# stm32.net
KiCad netlist of a schematic drawn in Altium Designer
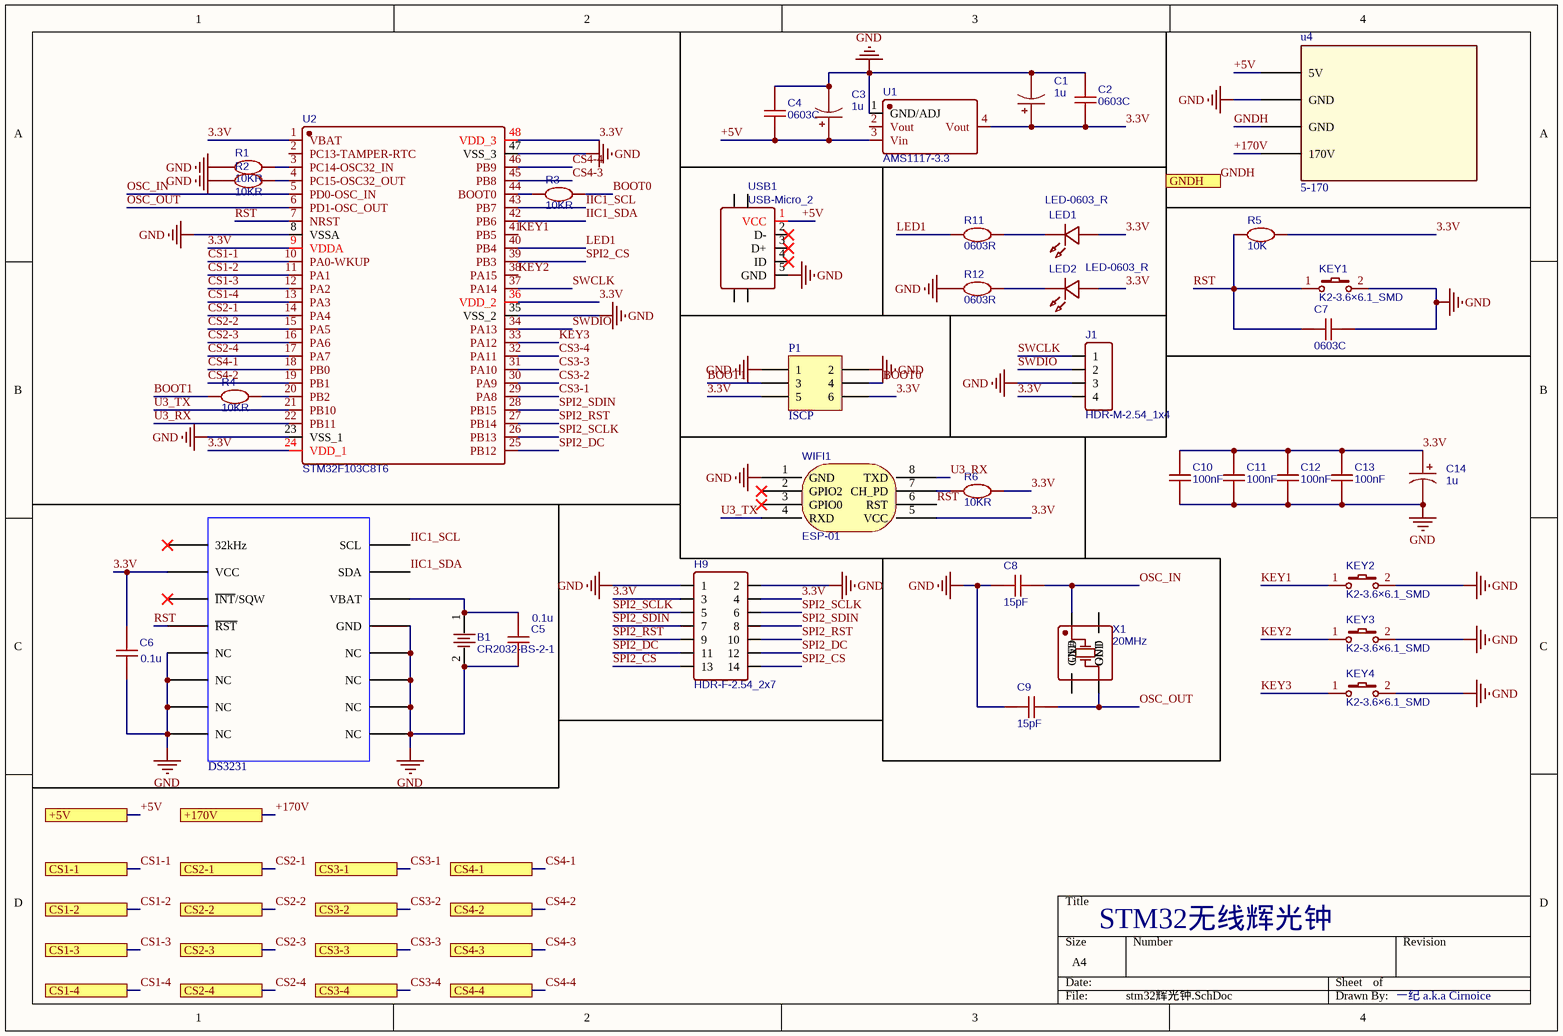
[diagram p0: stm32辉光钟.SchDoc]

(export (version "E")
  (design (tool "Eeschema 10.0.6"))
  (components
    (comp (ref "B1")
      (value "CR2032-BS-2-1")
      (footprint "BAT-TH_BS-2-1")
      (fields (field (name "BOM_MANUFACTURER PART") "BS-2-1") (field (name "BOM_SUPPLIER PART") "C70376"))
      (libsource (lib "Nixie_ESP32") (part "CR2032-BS-2-1"))
    )
    (comp (ref "C1")
      (value "1u")
      (footprint "CASE-A_3216")
      (fields (field (name "CONTRIBUTOR") "LCEDA_Lib"))
      (libsource (lib "Nixie_ESP32") (part "1u"))
    )
    (comp (ref "C2")
      (value "0603C")
      (footprint "C0603")
      (fields (field (name "CONTRIBUTOR") "LCEDA_Lib"))
      (libsource (lib "Nixie_ESP32") (part "0603C"))
    )
    (comp (ref "C3")
      (value "1u")
      (footprint "CASE-A_3216")
      (fields (field (name "CONTRIBUTOR") "LCEDA_Lib"))
      (libsource (lib "Nixie_ESP32") (part "1u"))
    )
    (comp (ref "C4")
      (value "0603C")
      (footprint "C0603")
      (fields (field (name "CONTRIBUTOR") "LCEDA_Lib"))
      (libsource (lib "Nixie_ESP32") (part "0603C"))
    )
    (comp (ref "C5")
      (value "0.1u")
      (footprint "C0603")
      (fields (field (name "CONTRIBUTOR") "LCEDA_Lib"))
      (libsource (lib "Nixie_ESP32") (part "0603C"))
    )
    (comp (ref "C6")
      (value "0.1u")
      (footprint "C0603")
      (fields (field (name "CONTRIBUTOR") "LCEDA_Lib"))
      (libsource (lib "Nixie_ESP32") (part "0603C"))
    )
    (comp (ref "C7")
      (value "0603C")
      (footprint "C0603")
      (fields (field (name "CONTRIBUTOR") "LCEDA_Lib"))
      (libsource (lib "Nixie_ESP32") (part "0603C"))
    )
    (comp (ref "C8")
      (value "15pF")
      (footprint "C0603")
      (fields (field (name "CONTRIBUTOR") "LCEDA_Lib"))
      (libsource (lib "Nixie_ESP32") (part "0603C"))
    )
    (comp (ref "C9")
      (value "15pF")
      (footprint "C0603")
      (fields (field (name "CONTRIBUTOR") "LCEDA_Lib"))
      (libsource (lib "Nixie_ESP32") (part "0603C"))
    )
    (comp (ref "C10")
      (value "100nF")
      (footprint "C0603")
      (fields (field (name "CONTRIBUTOR") "LCEDA_Lib"))
      (libsource (lib "Nixie_ESP32") (part "0603C"))
    )
    (comp (ref "C11")
      (value "100nF")
      (footprint "C0603")
      (fields (field (name "CONTRIBUTOR") "LCEDA_Lib"))
      (libsource (lib "Nixie_ESP32") (part "0603C"))
    )
    (comp (ref "C12")
      (value "100nF")
      (footprint "C0603")
      (fields (field (name "CONTRIBUTOR") "LCEDA_Lib"))
      (libsource (lib "Nixie_ESP32") (part "0603C"))
    )
    (comp (ref "C13")
      (value "100nF")
      (footprint "C0603")
      (fields (field (name "CONTRIBUTOR") "LCEDA_Lib"))
      (libsource (lib "Nixie_ESP32") (part "0603C"))
    )
    (comp (ref "C14")
      (value "1u")
      (footprint "CASE-A_3216")
      (fields (field (name "CONTRIBUTOR") "LCEDA_Lib"))
      (libsource (lib "Nixie_ESP32") (part "1u"))
    )
    (comp (ref "ds1") (value "DS3231") (footprint "DS3231") (libsource (lib "Nixie_ESP32") (part "DS3231")))
    (comp (ref "H9")
      (value "HDR-F-2.54_2x7")
      (footprint "HDR-F-2.54_2X7")
      (fields (field (name "BOM_SUPPLIER PART") "C38844") (field (name "CONTRIBUTOR") "LCEDA_Lib"))
      (libsource (lib "Nixie_ESP32") (part "HDR-F-2.54_2x7"))
    )
    (comp (ref "J1")
      (value "HDR-M-2.54_1x4")
      (footprint "HDR-M-2.54_1X4")
      (fields (field (name "BOM_SUPPLIER PART") "C124378") (field (name "CONTRIBUTOR") "LCEDA_Lib"))
      (libsource (lib "Nixie_ESP32") (part "HDR-M-2.54_1x4"))
    )
    (comp (ref "KEY1")
      (value "K2-3.6×6.1_SMD")
      (footprint "KEY-SMD_2P-L6.2-W3.6-LS8.0")
      (fields
        (field (name "BOM_SUPPLIER PART") "C118141")
        (field (name "BOM_MANUFACTURER PART") "K2-1107ST-A4SW-06")
        (field (name "CONTRIBUTOR") "LCEDA_Lib")
      )
      (libsource (lib "Nixie_ESP32") (part "K2-3.6×6.1_SMD"))
    )
    (comp (ref "KEY2")
      (value "K2-3.6×6.1_SMD")
      (footprint "KEY-SMD_2P-L6.2-W3.6-LS8.0")
      (fields
        (field (name "BOM_SUPPLIER PART") "C118141")
        (field (name "BOM_MANUFACTURER PART") "K2-1107ST-A4SW-06")
        (field (name "CONTRIBUTOR") "LCEDA_Lib")
      )
      (libsource (lib "Nixie_ESP32") (part "K2-3.6×6.1_SMD"))
    )
    (comp (ref "KEY3")
      (value "K2-3.6×6.1_SMD")
      (footprint "KEY-SMD_2P-L6.2-W3.6-LS8.0")
      (fields
        (field (name "BOM_SUPPLIER PART") "C118141")
        (field (name "BOM_MANUFACTURER PART") "K2-1107ST-A4SW-06")
        (field (name "CONTRIBUTOR") "LCEDA_Lib")
      )
      (libsource (lib "Nixie_ESP32") (part "K2-3.6×6.1_SMD"))
    )
    (comp (ref "KEY4")
      (value "K2-3.6×6.1_SMD")
      (footprint "KEY-SMD_2P-L6.2-W3.6-LS8.0")
      (fields
        (field (name "BOM_SUPPLIER PART") "C118141")
        (field (name "BOM_MANUFACTURER PART") "K2-1107ST-A4SW-06")
        (field (name "CONTRIBUTOR") "LCEDA_Lib")
      )
      (libsource (lib "Nixie_ESP32") (part "K2-3.6×6.1_SMD"))
    )
    (comp (ref "LED1")
      (value "LED-0603_R")
      (footprint "LED0603_RED")
      (fields
        (field (name "BOM_MANUFACTURER PART") "19-217/R6C-AL1M2VY/3T")
        (field (name "BOM_SUPPLIER PART") "C72044")
        (field (name "CONTRIBUTOR") "LCEDA_01")
      )
      (libsource (lib "Nixie_ESP32") (part "LED-0603_R"))
    )
    (comp (ref "LED2")
      (value "LED-0603_R")
      (footprint "LED0603_RED")
      (fields
        (field (name "BOM_MANUFACTURER PART") "19-217/R6C-AL1M2VY/3T")
        (field (name "BOM_SUPPLIER PART") "C72044")
        (field (name "CONTRIBUTOR") "LCEDA_01")
      )
      (libsource (lib "Nixie_ESP32") (part "LED-0603_R"))
    )
    (comp (ref "P1")
      (value "ISCP")
      (footprint "HDR2X3")
      (description "Header, 3-Pin, Dual row")
      (fields (field (name "PUBLISHER") "Altium Limited"))
      (libsource (lib "Nixie_ESP32") (part "Header 3X2"))
    )
    (comp (ref "R1")
      (value "10KR")
      (footprint "R0603")
      (fields (field (name "CONTRIBUTOR") "LCEDA_Lib"))
      (libsource (lib "Nixie_ESP32") (part "0603R"))
    )
    (comp (ref "R2")
      (value "10KR")
      (footprint "R0603")
      (fields (field (name "CONTRIBUTOR") "LCEDA_Lib"))
      (libsource (lib "Nixie_ESP32") (part "0603R"))
    )
    (comp (ref "R3")
      (value "10KR")
      (footprint "R0603")
      (fields (field (name "CONTRIBUTOR") "LCEDA_Lib"))
      (libsource (lib "Nixie_ESP32") (part "0603R"))
    )
    (comp (ref "R4")
      (value "10KR")
      (footprint "R0603")
      (fields (field (name "CONTRIBUTOR") "LCEDA_Lib"))
      (libsource (lib "Nixie_ESP32") (part "0603R"))
    )
    (comp (ref "R5")
      (value "10K")
      (footprint "R0603")
      (fields (field (name "CONTRIBUTOR") "LCEDA_Lib"))
      (libsource (lib "Nixie_ESP32") (part "0603R"))
    )
    (comp (ref "R6")
      (value "10KR")
      (footprint "R0603")
      (fields (field (name "CONTRIBUTOR") "LCEDA_Lib"))
      (libsource (lib "Nixie_ESP32") (part "0603R"))
    )
    (comp (ref "R11")
      (value "0603R")
      (footprint "R0603")
      (fields (field (name "CONTRIBUTOR") "LCEDA_Lib"))
      (libsource (lib "Nixie_ESP32") (part "0603R"))
    )
    (comp (ref "R12")
      (value "0603R")
      (footprint "R0603")
      (fields (field (name "CONTRIBUTOR") "LCEDA_Lib"))
      (libsource (lib "Nixie_ESP32") (part "0603R"))
    )
    (comp (ref "U1")
      (value "AMS1117-3.3")
      (footprint "SOT-223-3_L6.5-W3.4-P2.30-LS7.0-BR")
      (fields (field (name "BOM_SUPPLIER PART") "C6186"))
      (libsource (lib "Nixie_ESP32") (part "AMS1117-3.3"))
    )
    (comp (ref "U2")
      (value "STM32F103C8T6")
      (footprint "LQFP-48_L7.0-W7.0-P0.50-LS9.0-BL")
      (fields (field (name "BOM_SUPPLIER PART") "C8734"))
      (libsource (lib "Nixie_ESP32") (part "STM32F103C8T6"))
    )
    (comp (ref "u4") (value "5-170") (footprint "5-170V") (libsource (lib "Nixie_ESP32") (part "5-170")))
    (comp (ref "USB1")
      (value "USB-Micro_2")
      (footprint "MICRO-USB-SMD_5P_C40957")
      (fields (field (name "BOM_SUPPLIER PART") "C40957") (field (name "CONTRIBUTOR") "LCEDA_Lib"))
      (libsource (lib "Nixie_ESP32") (part "USB-Micro_2"))
    )
    (comp (ref "WIFI1")
      (value "ESP-01")
      (footprint "ESP-01")
      (fields (field (name "CONTRIBUTOR") "jishuhai"))
      (libsource (lib "Nixie_ESP32") (part "ESP-01"))
    )
    (comp (ref "X1")
      (value "20MHz")
      (footprint "CRYSTAL-SMD_4P-L3.2-W2.5-BL")
      (fields
        (field (name "BOM_SUPPLIER PART") "C172730")
        (field (name "BOM_MANUFACTURER PART") "SMD-3225_4P20MHZ20PF10PPM")
        (field (name "CONTRIBUTOR") "LCSC")
      )
      (libsource (lib "Nixie_ESP32") (part "20MHz"))
    )
  )
  (nets
    (net (code "1") (name "/+5V") (class "Default")
      (node (ref "C3") (pin "1") (pinfunction "1_1") (pintype "passive"))
      (node (ref "C4") (pin "1") (pinfunction "1_1") (pintype "passive"))
      (node (ref "U1") (pin "3") (pinfunction "Vin_3") (pintype "passive"))
      (node (ref "USB1") (pin "1") (pinfunction "VCC_1") (pintype "passive"))
      (node (ref "u4") (pin "1") (pinfunction "5V_1") (pintype "passive"))
    )
    (net (code "2") (name "/+170V") (class "Default")
      (node (ref "u4") (pin "4") (pinfunction "170V_4") (pintype "passive"))
    )
    (net (code "3") (name "/3.3V") (class "Default")
      (node (ref "C1") (pin "1") (pinfunction "1_1") (pintype "passive"))
      (node (ref "C10") (pin "2") (pinfunction "2_2") (pintype "passive"))
      (node (ref "C11") (pin "2") (pinfunction "2_2") (pintype "passive"))
      (node (ref "C12") (pin "2") (pinfunction "2_2") (pintype "passive"))
      (node (ref "C13") (pin "2") (pinfunction "2_2") (pintype "passive"))
      (node (ref "C14") (pin "1") (pinfunction "1_1") (pintype "passive"))
      (node (ref "C2") (pin "1") (pinfunction "1_1") (pintype "passive"))
      (node (ref "C6") (pin "2") (pinfunction "2_2") (pintype "passive"))
      (node (ref "H9") (pin "3") (pinfunction "3_3") (pintype "passive"))
      (node (ref "H9") (pin "4") (pinfunction "4_4") (pintype "passive"))
      (node (ref "J1") (pin "4") (pinfunction "4_4") (pintype "passive"))
      (node (ref "LED1") (pin "1") (pinfunction "1_1") (pintype "passive"))
      (node (ref "LED2") (pin "1") (pinfunction "1_1") (pintype "passive"))
      (node (ref "P1") (pin "5") (pinfunction "5_5") (pintype "passive"))
      (node (ref "P1") (pin "6") (pinfunction "6_6") (pintype "passive"))
      (node (ref "R5") (pin "2") (pinfunction "2_2") (pintype "passive"))
      (node (ref "R6") (pin "2") (pinfunction "2_2") (pintype "passive"))
      (node (ref "U1") (pin "4") (pinfunction "Vout_4") (pintype "passive"))
      (node (ref "U2") (pin "1") (pinfunction "VBAT_1") (pintype "passive"))
      (node (ref "U2") (pin "24") (pinfunction "VDD_1_24") (pintype "passive"))
      (node (ref "U2") (pin "36") (pinfunction "VDD_2_36") (pintype "passive"))
      (node (ref "U2") (pin "48") (pinfunction "VDD_3_48") (pintype "passive"))
      (node (ref "U2") (pin "9") (pinfunction "VDDA_9") (pintype "passive"))
      (node (ref "WIFI1") (pin "5") (pinfunction "VCC_5") (pintype "passive"))
      (node (ref "ds1") (pin "2") (pinfunction "VCC_2") (pintype "passive"))
    )
    (net (code "5") (name "/BOOT0") (class "Default")
      (node (ref "P1") (pin "4") (pinfunction "4_4") (pintype "passive"))
      (node (ref "R3") (pin "2") (pinfunction "2_2") (pintype "passive"))
    )
    (net (code "6") (name "/BOOT1") (class "Default")
      (node (ref "P1") (pin "3") (pinfunction "3_3") (pintype "passive"))
      (node (ref "R4") (pin "1") (pinfunction "1_1") (pintype "passive"))
    )
    (net (code "7") (name "/CS1-1") (class "Default")
      (node (ref "U2") (pin "10") (pinfunction "PA0-WKUP_10") (pintype "passive"))
    )
    (net (code "8") (name "/CS1-2") (class "Default")
      (node (ref "U2") (pin "11") (pinfunction "PA1_11") (pintype "passive"))
    )
    (net (code "9") (name "/CS1-3") (class "Default")
      (node (ref "U2") (pin "12") (pinfunction "PA2_12") (pintype "passive"))
    )
    (net (code "10") (name "/CS1-4") (class "Default")
      (node (ref "U2") (pin "13") (pinfunction "PA3_13") (pintype "passive"))
    )
    (net (code "11") (name "/CS2-1") (class "Default")
      (node (ref "U2") (pin "14") (pinfunction "PA4_14") (pintype "passive"))
    )
    (net (code "12") (name "/CS2-2") (class "Default")
      (node (ref "U2") (pin "15") (pinfunction "PA5_15") (pintype "passive"))
    )
    (net (code "13") (name "/CS2-3") (class "Default")
      (node (ref "U2") (pin "16") (pinfunction "PA6_16") (pintype "passive"))
    )
    (net (code "14") (name "/CS2-4") (class "Default")
      (node (ref "U2") (pin "17") (pinfunction "PA7_17") (pintype "passive"))
    )
    (net (code "15") (name "/CS3-1") (class "Default")
      (node (ref "U2") (pin "29") (pinfunction "PA8_29") (pintype "passive"))
    )
    (net (code "16") (name "/CS3-2") (class "Default")
      (node (ref "U2") (pin "30") (pinfunction "PA9_30") (pintype "passive"))
    )
    (net (code "17") (name "/CS3-3") (class "Default")
      (node (ref "U2") (pin "31") (pinfunction "PA10_31") (pintype "passive"))
    )
    (net (code "18") (name "/CS3-4") (class "Default")
      (node (ref "U2") (pin "32") (pinfunction "PA11_32") (pintype "passive"))
    )
    (net (code "19") (name "/CS4-1") (class "Default")
      (node (ref "U2") (pin "18") (pinfunction "PB0_18") (pintype "passive"))
    )
    (net (code "20") (name "/CS4-2") (class "Default")
      (node (ref "U2") (pin "19") (pinfunction "PB1_19") (pintype "passive"))
    )
    (net (code "21") (name "/CS4-3") (class "Default")
      (node (ref "U2") (pin "45") (pinfunction "PB8_45") (pintype "passive"))
    )
    (net (code "22") (name "/CS4-4") (class "Default")
      (node (ref "U2") (pin "46") (pinfunction "PB9_46") (pintype "passive"))
    )
    (net (code "23") (name "/GNDH") (class "Default")
      (node (ref "u4") (pin "3") (pinfunction "GND_3") (pintype "passive"))
    )
    (net (code "24") (name "/IIC1_SCL") (class "Default")
      (node (ref "U2") (pin "43") (pinfunction "PB7_43") (pintype "passive"))
      (node (ref "ds1") (pin "16") (pinfunction "SCL_16") (pintype "passive"))
    )
    (net (code "25") (name "/IIC1_SDA") (class "Default")
      (node (ref "U2") (pin "42") (pinfunction "PB6_42") (pintype "passive"))
      (node (ref "ds1") (pin "15") (pinfunction "SDA_15") (pintype "passive"))
    )
    (net (code "26") (name "/KEY1") (class "Default")
      (node (ref "KEY2") (pin "1") (pinfunction "1_1") (pintype "passive"))
      (node (ref "U2") (pin "41") (pinfunction "PB5_41") (pintype "passive"))
    )
    (net (code "27") (name "/KEY2") (class "Default")
      (node (ref "KEY3") (pin "1") (pinfunction "1_1") (pintype "passive"))
      (node (ref "U2") (pin "38") (pinfunction "PA15_38") (pintype "passive"))
    )
    (net (code "28") (name "/KEY3") (class "Default")
      (node (ref "KEY4") (pin "1") (pinfunction "1_1") (pintype "passive"))
      (node (ref "U2") (pin "33") (pinfunction "PA12_33") (pintype "passive"))
    )
    (net (code "29") (name "/LED1") (class "Default")
      (node (ref "R11") (pin "1") (pinfunction "1_1") (pintype "passive"))
      (node (ref "U2") (pin "40") (pinfunction "PB4_40") (pintype "passive"))
    )
    (net (code "30") (name "/OSC_IN") (class "Default")
      (node (ref "C8") (pin "2") (pinfunction "2_2") (pintype "passive"))
      (node (ref "U2") (pin "5") (pinfunction "PD0-OSC_IN_5") (pintype "passive"))
      (node (ref "X1") (pin "1") (pinfunction "OE#_1") (pintype "passive"))
    )
    (net (code "31") (name "/OSC_OUT") (class "Default")
      (node (ref "C9") (pin "2") (pinfunction "2_2") (pintype "passive"))
      (node (ref "U2") (pin "6") (pinfunction "PD1-OSC_OUT_6") (pintype "passive"))
      (node (ref "X1") (pin "3") (pinfunction "OUT_3") (pintype "passive"))
    )
    (net (code "32") (name "/RST") (class "Default")
      (node (ref "C7") (pin "1") (pinfunction "1_1") (pintype "passive"))
      (node (ref "KEY1") (pin "1") (pinfunction "1_1") (pintype "passive"))
      (node (ref "R5") (pin "1") (pinfunction "1_1") (pintype "passive"))
      (node (ref "U2") (pin "7") (pinfunction "NRST_7") (pintype "passive"))
      (node (ref "WIFI1") (pin "6") (pinfunction "RST_6") (pintype "passive"))
      (node (ref "ds1") (pin "4") (pinfunction "~{RST}_4") (pintype "passive"))
    )
    (net (code "33") (name "/SPI2_CS") (class "Default")
      (node (ref "H9") (pin "13") (pinfunction "13_13") (pintype "passive"))
      (node (ref "H9") (pin "14") (pinfunction "14_14") (pintype "passive"))
      (node (ref "U2") (pin "39") (pinfunction "PB3_39") (pintype "passive"))
    )
    (net (code "34") (name "/SPI2_DC") (class "Default")
      (node (ref "H9") (pin "11") (pinfunction "11_11") (pintype "passive"))
      (node (ref "H9") (pin "12") (pinfunction "12_12") (pintype "passive"))
      (node (ref "U2") (pin "25") (pinfunction "PB12_25") (pintype "passive"))
    )
    (net (code "35") (name "/SPI2_RST") (class "Default")
      (node (ref "H9") (pin "10") (pinfunction "10_10") (pintype "passive"))
      (node (ref "H9") (pin "9") (pinfunction "9_9") (pintype "passive"))
      (node (ref "U2") (pin "27") (pinfunction "PB14_27") (pintype "passive"))
    )
    (net (code "36") (name "/SPI2_SCLK") (class "Default")
      (node (ref "H9") (pin "5") (pinfunction "5_5") (pintype "passive"))
      (node (ref "H9") (pin "6") (pinfunction "6_6") (pintype "passive"))
      (node (ref "U2") (pin "26") (pinfunction "PB13_26") (pintype "passive"))
    )
    (net (code "37") (name "/SPI2_SDIN") (class "Default")
      (node (ref "H9") (pin "7") (pinfunction "7_7") (pintype "passive"))
      (node (ref "H9") (pin "8") (pinfunction "8_8") (pintype "passive"))
      (node (ref "U2") (pin "28") (pinfunction "PB15_28") (pintype "passive"))
    )
    (net (code "38") (name "/SWCLK") (class "Default")
      (node (ref "J1") (pin "1") (pinfunction "1_1") (pintype "passive"))
      (node (ref "U2") (pin "37") (pinfunction "PA14_37") (pintype "passive"))
    )
    (net (code "39") (name "/SWDIO") (class "Default")
      (node (ref "J1") (pin "2") (pinfunction "2_2") (pintype "passive"))
      (node (ref "U2") (pin "34") (pinfunction "PA13_34") (pintype "passive"))
    )
    (net (code "40") (name "/U3_RX") (class "Default")
      (node (ref "U2") (pin "22") (pinfunction "PB11_22") (pintype "passive"))
      (node (ref "WIFI1") (pin "8") (pinfunction "TXD_8") (pintype "passive"))
    )
    (net (code "41") (name "/U3_TX") (class "Default")
      (node (ref "U2") (pin "21") (pinfunction "PB10_21") (pintype "passive"))
      (node (ref "WIFI1") (pin "4") (pinfunction "RXD_4") (pintype "passive"))
    )
    (net (code "42") (name "GND") (class "Default")
      (node (ref "B1") (pin "2") (pinfunction "2_2") (pintype "passive"))
      (node (ref "C1") (pin "2") (pinfunction "2_2") (pintype "passive"))
      (node (ref "C10") (pin "1") (pinfunction "1_1") (pintype "passive"))
      (node (ref "C11") (pin "1") (pinfunction "1_1") (pintype "passive"))
      (node (ref "C12") (pin "1") (pinfunction "1_1") (pintype "passive"))
      (node (ref "C13") (pin "1") (pinfunction "1_1") (pintype "passive"))
      (node (ref "C14") (pin "2") (pinfunction "2_2") (pintype "passive"))
      (node (ref "C2") (pin "2") (pinfunction "2_2") (pintype "passive"))
      (node (ref "C3") (pin "2") (pinfunction "2_2") (pintype "passive"))
      (node (ref "C4") (pin "2") (pinfunction "2_2") (pintype "passive"))
      (node (ref "C5") (pin "1") (pinfunction "1_1") (pintype "passive"))
      (node (ref "C6") (pin "1") (pinfunction "1_1") (pintype "passive"))
      (node (ref "C7") (pin "2") (pinfunction "2_2") (pintype "passive"))
      (node (ref "C8") (pin "1") (pinfunction "1_1") (pintype "passive"))
      (node (ref "C9") (pin "1") (pinfunction "1_1") (pintype "passive"))
      (node (ref "H9") (pin "1") (pinfunction "1_1") (pintype "passive"))
      (node (ref "H9") (pin "2") (pinfunction "2_2") (pintype "passive"))
      (node (ref "J1") (pin "3") (pinfunction "3_3") (pintype "passive"))
      (node (ref "KEY1") (pin "2") (pinfunction "2_2") (pintype "passive"))
      (node (ref "KEY2") (pin "2") (pinfunction "2_2") (pintype "passive"))
      (node (ref "KEY3") (pin "2") (pinfunction "2_2") (pintype "passive"))
      (node (ref "KEY4") (pin "2") (pinfunction "2_2") (pintype "passive"))
      (node (ref "P1") (pin "1") (pinfunction "1_1") (pintype "passive"))
      (node (ref "P1") (pin "2") (pinfunction "2_2") (pintype "passive"))
      (node (ref "R1") (pin "1") (pinfunction "1_1") (pintype "passive"))
      (node (ref "R12") (pin "1") (pinfunction "1_1") (pintype "passive"))
      (node (ref "R2") (pin "1") (pinfunction "1_1") (pintype "passive"))
      (node (ref "U1") (pin "1") (pinfunction "GND/ADJ_1") (pintype "passive"))
      (node (ref "U2") (pin "23") (pinfunction "VSS_1_23") (pintype "passive"))
      (node (ref "U2") (pin "35") (pinfunction "VSS_2_35") (pintype "passive"))
      (node (ref "U2") (pin "47") (pinfunction "VSS_3_47") (pintype "passive"))
      (node (ref "U2") (pin "8") (pinfunction "VSSA_8") (pintype "passive"))
      (node (ref "USB1") (pin "5") (pinfunction "GND_5") (pintype "passive"))
      (node (ref "WIFI1") (pin "1") (pinfunction "GND_1") (pintype "passive"))
      (node (ref "ds1") (pin "10") (pinfunction "NC_10") (pintype "passive"))
      (node (ref "ds1") (pin "11") (pinfunction "NC_11") (pintype "passive"))
      (node (ref "ds1") (pin "12") (pinfunction "NC_12") (pintype "passive"))
      (node (ref "ds1") (pin "13") (pinfunction "GND_13") (pintype "passive"))
      (node (ref "ds1") (pin "5") (pinfunction "NC_5") (pintype "passive"))
      (node (ref "ds1") (pin "6") (pinfunction "NC_6") (pintype "passive"))
      (node (ref "ds1") (pin "7") (pinfunction "NC_7") (pintype "passive"))
      (node (ref "ds1") (pin "8") (pinfunction "NC_8") (pintype "passive"))
      (node (ref "ds1") (pin "9") (pinfunction "NC_9") (pintype "passive"))
      (node (ref "u4") (pin "2") (pinfunction "GND_2") (pintype "passive"))
    )
    (net (code "43") (name "Net-(LED1-Pad2)") (class "Default")
      (node (ref "LED1") (pin "2") (pinfunction "2_2") (pintype "passive"))
      (node (ref "R11") (pin "2") (pinfunction "2_2") (pintype "passive"))
    )
    (net (code "44") (name "Net-(LED2-Pad2)") (class "Default")
      (node (ref "LED2") (pin "2") (pinfunction "2_2") (pintype "passive"))
      (node (ref "R12") (pin "2") (pinfunction "2_2") (pintype "passive"))
    )
    (net (code "45") (name "Net-(U2-BOOT0)") (class "Default")
      (node (ref "R3") (pin "1") (pinfunction "1_1") (pintype "passive"))
      (node (ref "U2") (pin "44") (pinfunction "BOOT0_44") (pintype "passive"))
    )
    (net (code "46") (name "Net-(U2-PB2)") (class "Default")
      (node (ref "R4") (pin "2") (pinfunction "2_2") (pintype "passive"))
      (node (ref "U2") (pin "20") (pinfunction "PB2_20") (pintype "passive"))
    )
    (net (code "47") (name "Net-(U2-PC14-OSC32_IN)") (class "Default")
      (node (ref "R1") (pin "2") (pinfunction "2_2") (pintype "passive"))
      (node (ref "U2") (pin "3") (pinfunction "PC14-OSC32_IN_3") (pintype "passive"))
    )
    (net (code "48") (name "Net-(U2-PC15-OSC32_OUT)") (class "Default")
      (node (ref "R2") (pin "2") (pinfunction "2_2") (pintype "passive"))
      (node (ref "U2") (pin "4") (pinfunction "PC15-OSC32_OUT_4") (pintype "passive"))
    )
    (net (code "49") (name "Net-(WIFI1-CH_PD)") (class "Default")
      (node (ref "R6") (pin "1") (pinfunction "1_1") (pintype "passive"))
      (node (ref "WIFI1") (pin "7") (pinfunction "CH_PD_7") (pintype "passive"))
    )
    (net (code "50") (name "Net-(ds1-VBAT)") (class "Default")
      (node (ref "B1") (pin "1") (pinfunction "1_1") (pintype "passive"))
      (node (ref "C5") (pin "2") (pinfunction "2_2") (pintype "passive"))
      (node (ref "ds1") (pin "14") (pinfunction "VBAT_14") (pintype "passive"))
    )
    (net (code "51") (name "unconnected-(U1-Vout-Pad2)") (class "Default")
      (node (ref "U1") (pin "2") (pinfunction "Vout_2") (pintype "passive"))
    )
    (net (code "52") (name "unconnected-(U2-PC13-TAMPER-RTC-Pad2)") (class "Default")
      (node (ref "U2") (pin "2") (pinfunction "PC13-TAMPER-RTC_2") (pintype "passive"))
    )
    (net (code "53") (name "unconnected-(USB1-D+-Pad3)") (class "Default")
      (node (ref "USB1") (pin "3") (pinfunction "D+_3") (pintype "passive+no_connect"))
    )
    (net (code "54") (name "unconnected-(USB1-D--Pad2)") (class "Default")
      (node (ref "USB1") (pin "2") (pinfunction "D-_2") (pintype "passive+no_connect"))
    )
    (net (code "55") (name "unconnected-(USB1-ID-Pad4)") (class "Default")
      (node (ref "USB1") (pin "4") (pinfunction "ID_4") (pintype "passive+no_connect"))
    )
    (net (code "56") (name "unconnected-(USB1-SH1-Pad8)") (class "Default")
      (node (ref "USB1") (pin "8") (pinfunction "SH1_8") (pintype "passive"))
    )
    (net (code "57") (name "unconnected-(USB1-SH2-Pad9)") (class "Default")
      (node (ref "USB1") (pin "9") (pinfunction "SH2_9") (pintype "passive"))
    )
    (net (code "58") (name "unconnected-(USB1-SH3-Pad6)") (class "Default")
      (node (ref "USB1") (pin "6") (pinfunction "SH3_6") (pintype "passive"))
    )
    (net (code "59") (name "unconnected-(USB1-SH4-Pad7)") (class "Default")
      (node (ref "USB1") (pin "7") (pinfunction "SH4_7") (pintype "passive"))
    )
    (net (code "60") (name "unconnected-(WIFI1-GPIO0-Pad3)") (class "Default")
      (node (ref "WIFI1") (pin "3") (pinfunction "GPIO0_3") (pintype "passive+no_connect"))
    )
    (net (code "61") (name "unconnected-(WIFI1-GPIO2-Pad2)") (class "Default")
      (node (ref "WIFI1") (pin "2") (pinfunction "GPIO2_2") (pintype "passive+no_connect"))
    )
    (net (code "62") (name "unconnected-(X1-GND-Pad2)") (class "Default")
      (node (ref "X1") (pin "2") (pinfunction "GND_2") (pintype "passive"))
    )
    (net (code "63") (name "unconnected-(X1-GND-Pad4)") (class "Default")
      (node (ref "X1") (pin "4") (pinfunction "GND_4") (pintype "passive"))
    )
    (net (code "64") (name "unconnected-(ds1-32kHz-Pad1)") (class "Default")
      (node (ref "ds1") (pin "1") (pinfunction "32kHz_1") (pintype "passive+no_connect"))
    )
    (net (code "65") (name "unconnected-(ds1-~{INT}{slash}SQW-Pad3)") (class "Default")
      (node (ref "ds1") (pin "3") (pinfunction "~{INT}/SQW_3") (pintype "passive+no_connect"))
    )
  )
)
